# InductiveSensor.net
KiCad netlist of a schematic drawn in Altium Designer
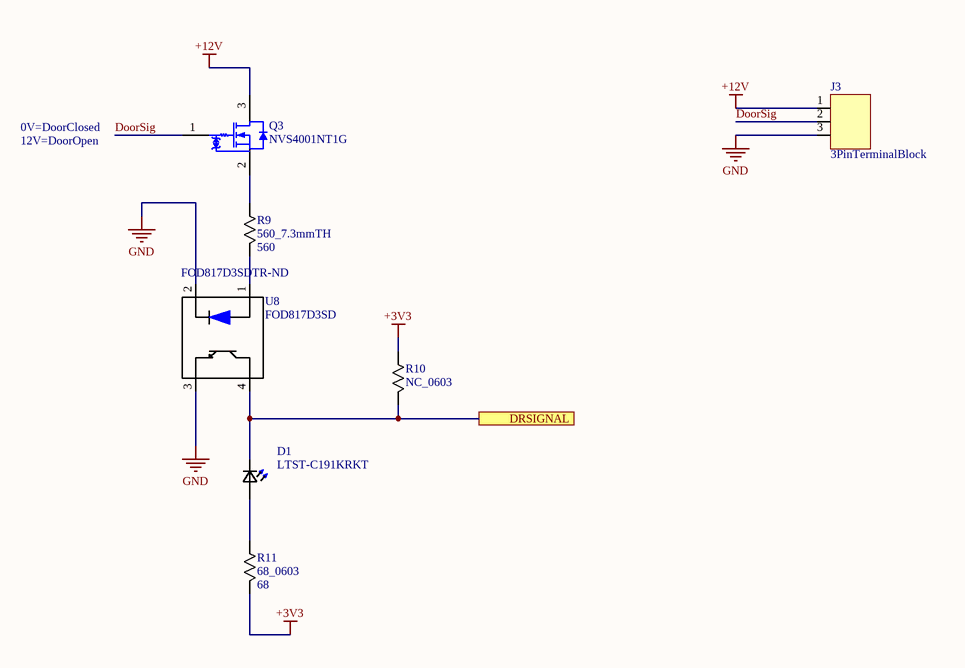
[diagram p0: InductiveSensor.SchDoc]

(export (version "E")
  (design (tool "Eeschema 10.0.6"))
  (components
    (comp (ref "D1")
      (value "LTST-C191KRKT")
      (footprint "0603")
      (description "LED; SMD; 0603; red; 18-54mcd; 1.6x0.8x0.55mm; 130Â°; 2Ã·2.4V; 20mA")
      (fields (field (name "MF") "Lite-On"))
      (libsource (lib "Diodes") (part "LTST-C191KRKT"))
    )
    (comp (ref "J3")
      (value "3PinTerminalBlock")
      (footprint "3 POS 5mm Pitch")
      (description "3 Position terminal block")
      (libsource (lib "Connectors") (part "3PinTerminalBlock"))
    )
    (comp (ref "Q3")
      (value "NVS4001NT1G")
      (footprint "ONSC-SC-70-3-419-04_V")
      (description "Small Signal MOSFET, 30 V, 270 mA, N-Channel, 3-Pin SC70, Pb-Free, Tape and Reel")
      (fields (field (name "MANUFACTURER") "On Semiconductor"))
      (libsource (lib "ON Semi MOSFETs") (part "NVS4001NT1G"))
    )
    (comp (ref "R9")
      (value "560_7.3mmTH")
      (footprint "7.3mm Through Hole")
      (fields
        (field (name "MANUFACTURER") "Stackpole Electronics")
        (field (name "MANUFACTURER PART NUMBER") "CFM12JT560R")
        (field (name "TOLERANCE") "5%")
        (field (name "RESISTANCE") "560")
      )
      (libsource (lib "Resistors") (part "560_7.3mmTH"))
    )
    (comp (ref "R10") (value "NC_0603") (footprint "0603") (libsource (lib "Resistors") (part "NC_0603")))
    (comp (ref "R11")
      (value "68_0603")
      (footprint "0603")
      (fields
        (field (name "MANUFACTURER") "Vishay")
        (field (name "MANUFACTURER PART NUMBER") "CRCW060368R0FKEA")
        (field (name "TOLERANCE") "1%")
        (field (name "RESISTANCE") "68")
      )
      (libsource (lib "Resistors") (part "68_0603"))
    )
    (comp (ref "U8")
      (value "FOD817D3SD")
      (footprint "FOD817D3SD")
      (description "OPTOISOLATOR 5KV TRANSISTOR 4SMD 20mA/1.2V saturation")
      (fields
        (field (name "MANUFACTURER") "ON Semiconductor / Fairchild")
        (field (name "SUPPLIER PART NUMBER 1") "FOD817D3SDTR-ND")
      )
      (libsource (lib "Optocouplers") (part "FOD817D3SD"))
    )
  )
  (nets
    (net (code "1") (name "+3V3") (class "Default")
      (node (ref "R10") (pin "2") (pinfunction "2_2") (pintype "passive"))
      (node (ref "R11") (pin "1") (pinfunction "1_1") (pintype "passive"))
    )
    (net (code "2") (name "+12V") (class "Default")
      (node (ref "J3") (pin "1") (pintype "passive"))
      (node (ref "Q3") (pin "3") (pinfunction "D_3") (pintype "passive"))
    )
    (net (code "3") (name "/DRSIGNAL") (class "Default")
      (node (ref "D1") (pin "1") (pinfunction "K2_1") (pintype "passive"))
      (node (ref "R10") (pin "1") (pinfunction "1_1") (pintype "passive"))
      (node (ref "U8") (pin "4") (pinfunction "COLLECTOR_4") (pintype "bidirectional"))
    )
    (net (code "4") (name "/DoorSig") (class "Default")
      (node (ref "J3") (pin "2") (pintype "passive"))
      (node (ref "Q3") (pin "1") (pinfunction "G_1") (pintype "passive"))
    )
    (net (code "5") (name "GND") (class "Default")
      (node (ref "J3") (pin "3") (pintype "passive"))
      (node (ref "U8") (pin "2") (pinfunction "CATHODE_2") (pintype "bidirectional"))
      (node (ref "U8") (pin "3") (pinfunction "EMITER_3") (pintype "bidirectional"))
    )
    (net (code "6") (name "Net-(D1-A2)") (class "Default")
      (node (ref "D1") (pin "2") (pinfunction "A2_2") (pintype "passive"))
      (node (ref "R11") (pin "2") (pinfunction "2_2") (pintype "passive"))
    )
    (net (code "7") (name "Net-(Q3-S)") (class "Default")
      (node (ref "Q3") (pin "2") (pinfunction "S_2") (pintype "passive"))
      (node (ref "R9") (pin "2") (pinfunction "2_2") (pintype "passive"))
    )
    (net (code "8") (name "Net-(U8-ANODE)") (class "Default")
      (node (ref "R9") (pin "1") (pinfunction "1_1") (pintype "passive"))
      (node (ref "U8") (pin "1") (pinfunction "ANODE_1") (pintype "bidirectional"))
    )
  )
)
